# LB_BIT_iX_1IN_1OUT-XXL-v03_1_1x.net
KiCad netlist of a schematic drawn in EAGLE
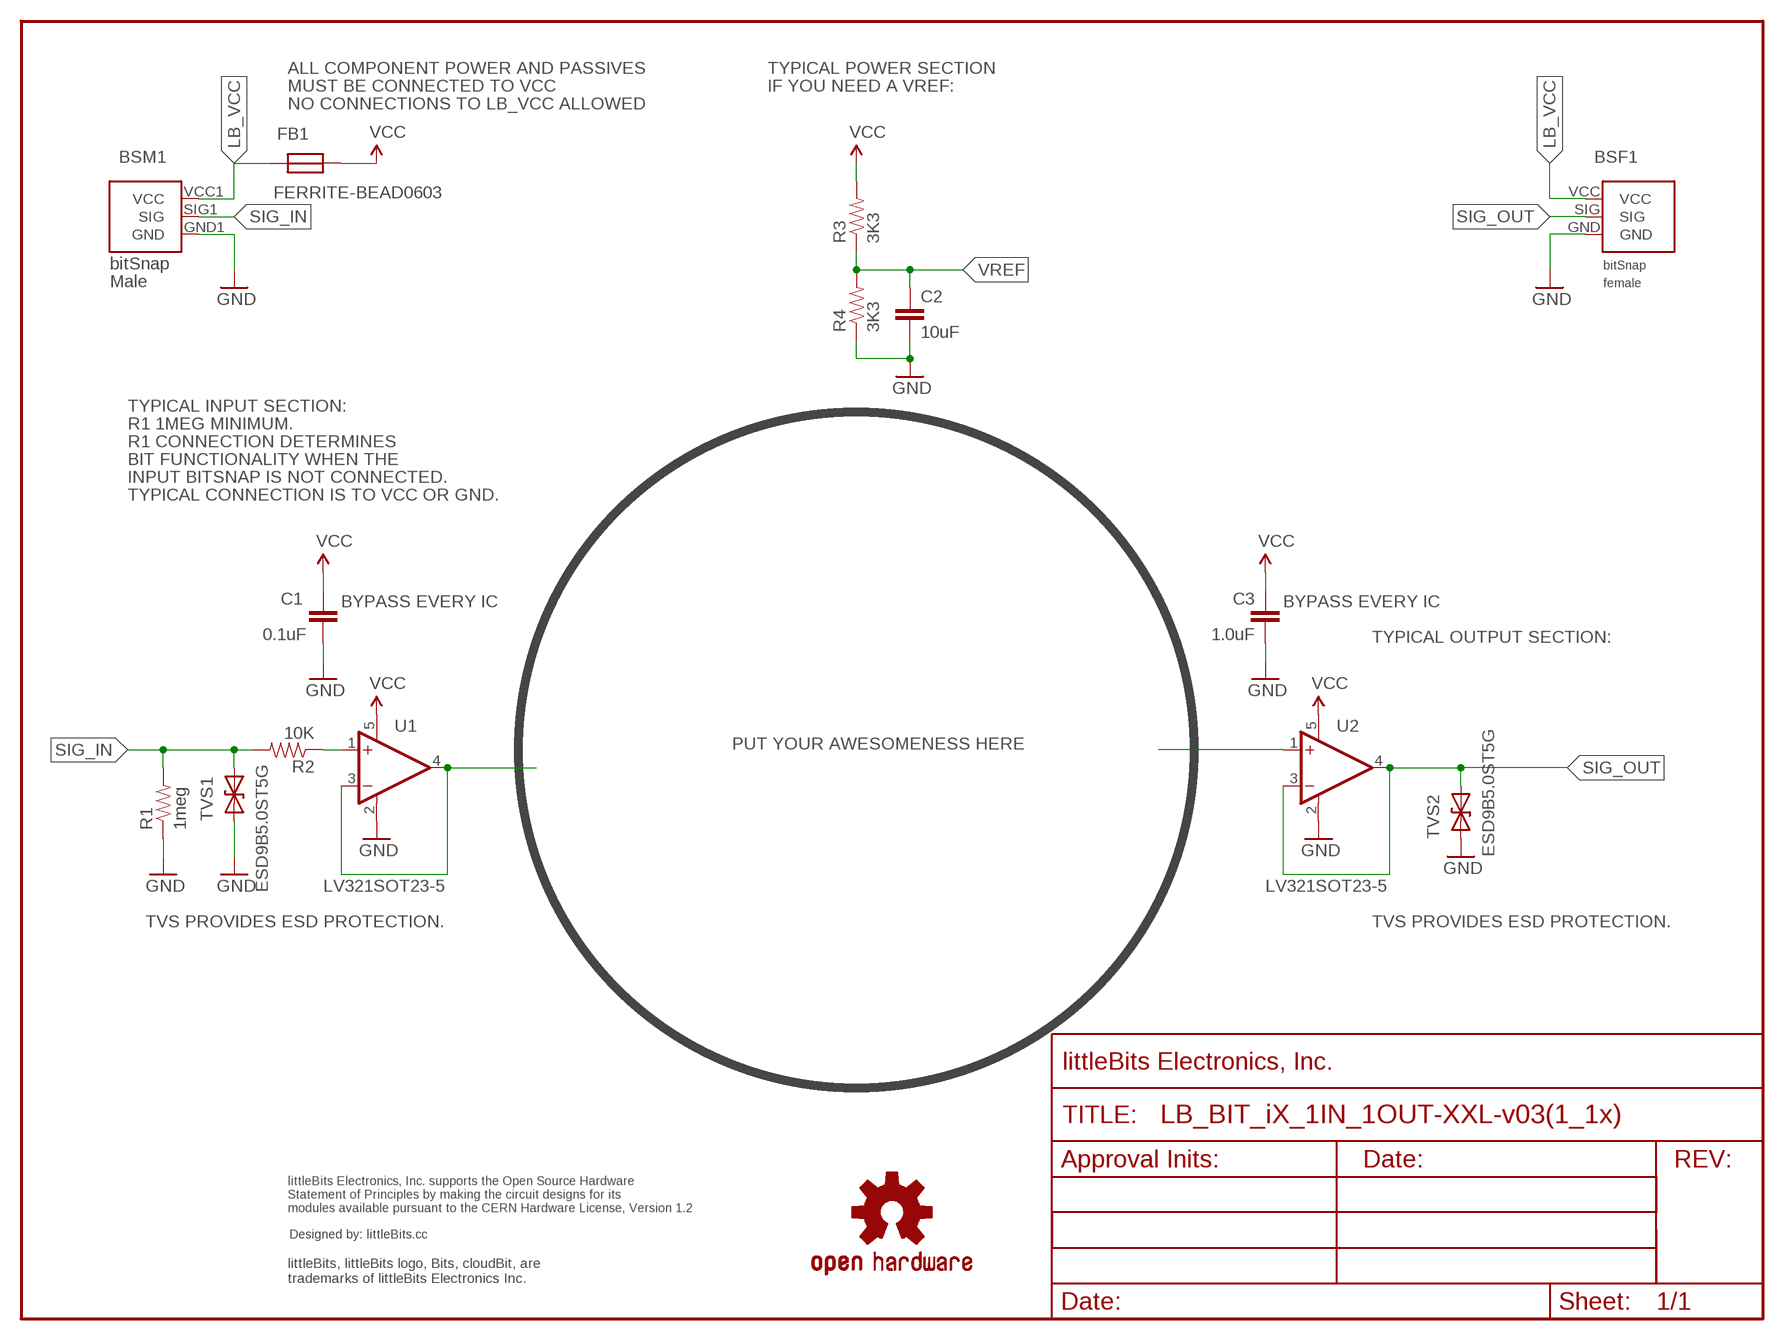
[diagram p0: schematic, sheet 1]

(export (version "E")
  (design (tool "Eeschema 10.0.6"))
  (components
    (comp (ref "BSF1")
      (value "BITSNAP_V03_FEMALE")
      (footprint "eagle-import:BITSNAP_V03_FEMALE")
      (libsource (lib "eagle-import") (part "BITSNAP_V03_FEMALE"))
    )
    (comp (ref "BSM1")
      (value "BITSNAP_V03_MALE")
      (footprint "eagle-import:BITSNAP_V03_MALE")
      (libsource (lib "eagle-import") (part "BITSNAP_V03_MALE"))
    )
    (comp (ref "C1")
      (value "0.1uF")
      (footprint "eagle-import:CAP-0603")
      (libsource (lib "eagle-import") (part "CAPCAP-0603"))
    )
    (comp (ref "C2")
      (value "10uF")
      (footprint "eagle-import:CAP-0603")
      (libsource (lib "eagle-import") (part "CAPCAP-0603"))
    )
    (comp (ref "C3")
      (value "1.0uF")
      (footprint "eagle-import:CAP-0603")
      (libsource (lib "eagle-import") (part "CAPCAP-0603"))
    )
    (comp (ref "FB1")
      (value "FERRITE-BEAD0603")
      (footprint "eagle-import:R0603")
      (libsource (lib "eagle-import") (part "FERRITE-BEAD0603"))
    )
    (comp (ref "R1")
      (value "1meg")
      (footprint "eagle-import:RES-0603")
      (libsource (lib "eagle-import") (part "RESISTOR0603"))
    )
    (comp (ref "R2")
      (value "10K")
      (footprint "eagle-import:RES-0603")
      (libsource (lib "eagle-import") (part "RESISTOR0603"))
    )
    (comp (ref "R3")
      (value "3K3")
      (footprint "eagle-import:RES-0603")
      (libsource (lib "eagle-import") (part "RESISTOR0603"))
    )
    (comp (ref "R4")
      (value "3K3")
      (footprint "eagle-import:RES-0603")
      (libsource (lib "eagle-import") (part "RESISTOR0603"))
    )
    (comp (ref "TVS1")
      (value "ESD9B5.0ST5G")
      (footprint "eagle-import:SOD-923")
      (libsource (lib "eagle-import") (part "DIODE-TVSSOD-923"))
    )
    (comp (ref "TVS2")
      (value "ESD9B5.0ST5G")
      (footprint "eagle-import:SOD-923")
      (libsource (lib "eagle-import") (part "DIODE-TVSSOD-923"))
    )
    (comp (ref "U$1")
      (value "OSHW-LOGOL")
      (footprint "eagle-import:OSHW-LOGO-L")
      (libsource (lib "eagle-import") (part "OSHW-LOGOL"))
    )
    (comp (ref "U$2")
      (value "OSHWCREDIT")
      (footprint "eagle-import:OSHWCREDIT")
      (libsource (lib "eagle-import") (part "OSHWCREDIT"))
    )
    (comp (ref "U$3")
      (value "FRAME-LETTER")
      (footprint "eagle-import:FABDWG01-OHW")
      (libsource (lib "eagle-import") (part "FRAME-LETTER"))
    )
    (comp (ref "U1")
      (value "LV321SOT23-5")
      (footprint "eagle-import:SOT23-5")
      (libsource (lib "eagle-import") (part "LV321SOT23-5"))
    )
    (comp (ref "U2")
      (value "LV321SOT23-5")
      (footprint "eagle-import:SOT23-5")
      (libsource (lib "eagle-import") (part "LV321SOT23-5"))
    )
  )
  (nets
    (net (code "1") (name "GND") (class "Default")
      (node (ref "BSF1") (pin "GND") (pinfunction "GND_GND") (pintype "bidirectional"))
      (node (ref "BSM1") (pin "GND1") (pinfunction "GND_GND1") (pintype "bidirectional"))
      (node (ref "C1") (pin "2") (pinfunction "2_2") (pintype "passive"))
      (node (ref "C2") (pin "2") (pinfunction "2_2") (pintype "passive"))
      (node (ref "C3") (pin "1") (pinfunction "1_1") (pintype "passive"))
      (node (ref "R1") (pin "1") (pinfunction "1_1") (pintype "passive"))
      (node (ref "R4") (pin "1") (pinfunction "1_1") (pintype "passive"))
      (node (ref "TVS1") (pin "1") (pinfunction "A_1") (pintype "passive"))
      (node (ref "TVS2") (pin "1") (pinfunction "A_1") (pintype "passive"))
      (node (ref "U1") (pin "2") (pinfunction "V-_2") (pintype "power_in"))
      (node (ref "U2") (pin "2") (pinfunction "V-_2") (pintype "power_in"))
    )
    (net (code "2") (name "LB_VCC") (class "Default")
      (node (ref "BSF1") (pin "VCC") (pinfunction "VCC_VCC") (pintype "bidirectional"))
      (node (ref "BSM1") (pin "VCC1") (pinfunction "VCC_VCC1") (pintype "bidirectional"))
      (node (ref "FB1") (pin "2") (pinfunction "P$2_2") (pintype "bidirectional"))
    )
    (net (code "3") (name "Net-(U1-+IN)") (class "Default")
      (node (ref "R2") (pin "1") (pinfunction "1_1") (pintype "passive"))
      (node (ref "U1") (pin "1") (pinfunction "+IN_1") (pintype "input"))
    )
    (net (code "4") (name "Net-(U1--IN)") (class "Default")
      (node (ref "U1") (pin "3") (pinfunction "-IN_3") (pintype "input"))
      (node (ref "U1") (pin "4") (pinfunction "OUT_4") (pintype "output"))
    )
    (net (code "5") (name "SIG_IN") (class "Default")
      (node (ref "BSM1") (pin "SIG1") (pinfunction "SIG_SIG1") (pintype "bidirectional"))
      (node (ref "R1") (pin "2") (pinfunction "2_2") (pintype "passive"))
      (node (ref "R2") (pin "2") (pinfunction "2_2") (pintype "passive"))
      (node (ref "TVS1") (pin "2") (pinfunction "C_2") (pintype "passive"))
    )
    (net (code "6") (name "SIG_OUT") (class "Default")
      (node (ref "BSF1") (pin "SIG") (pinfunction "SIG_SIG") (pintype "bidirectional"))
      (node (ref "TVS2") (pin "2") (pinfunction "C_2") (pintype "passive"))
      (node (ref "U2") (pin "3") (pinfunction "-IN_3") (pintype "input"))
      (node (ref "U2") (pin "4") (pinfunction "OUT_4") (pintype "output"))
    )
    (net (code "7") (name "VCC") (class "Default")
      (node (ref "C1") (pin "1") (pinfunction "1_1") (pintype "passive"))
      (node (ref "C3") (pin "2") (pinfunction "2_2") (pintype "passive"))
      (node (ref "FB1") (pin "1") (pinfunction "P$1_1") (pintype "bidirectional"))
      (node (ref "R3") (pin "2") (pinfunction "2_2") (pintype "passive"))
      (node (ref "U1") (pin "5") (pinfunction "V+_5") (pintype "power_in"))
      (node (ref "U2") (pin "5") (pinfunction "V+_5") (pintype "power_in"))
    )
    (net (code "8") (name "VREF") (class "Default")
      (node (ref "C2") (pin "1") (pinfunction "1_1") (pintype "passive"))
      (node (ref "R3") (pin "1") (pinfunction "1_1") (pintype "passive"))
      (node (ref "R4") (pin "2") (pinfunction "2_2") (pintype "passive"))
    )
    (net (code "9") (name "unconnected-(U2-+IN-Pad1)") (class "Default")
      (node (ref "U2") (pin "1") (pinfunction "+IN_1") (pintype "input"))
    )
  )
)
